# Power_v0.net
KiCad netlist of a schematic drawn in Altium Designer
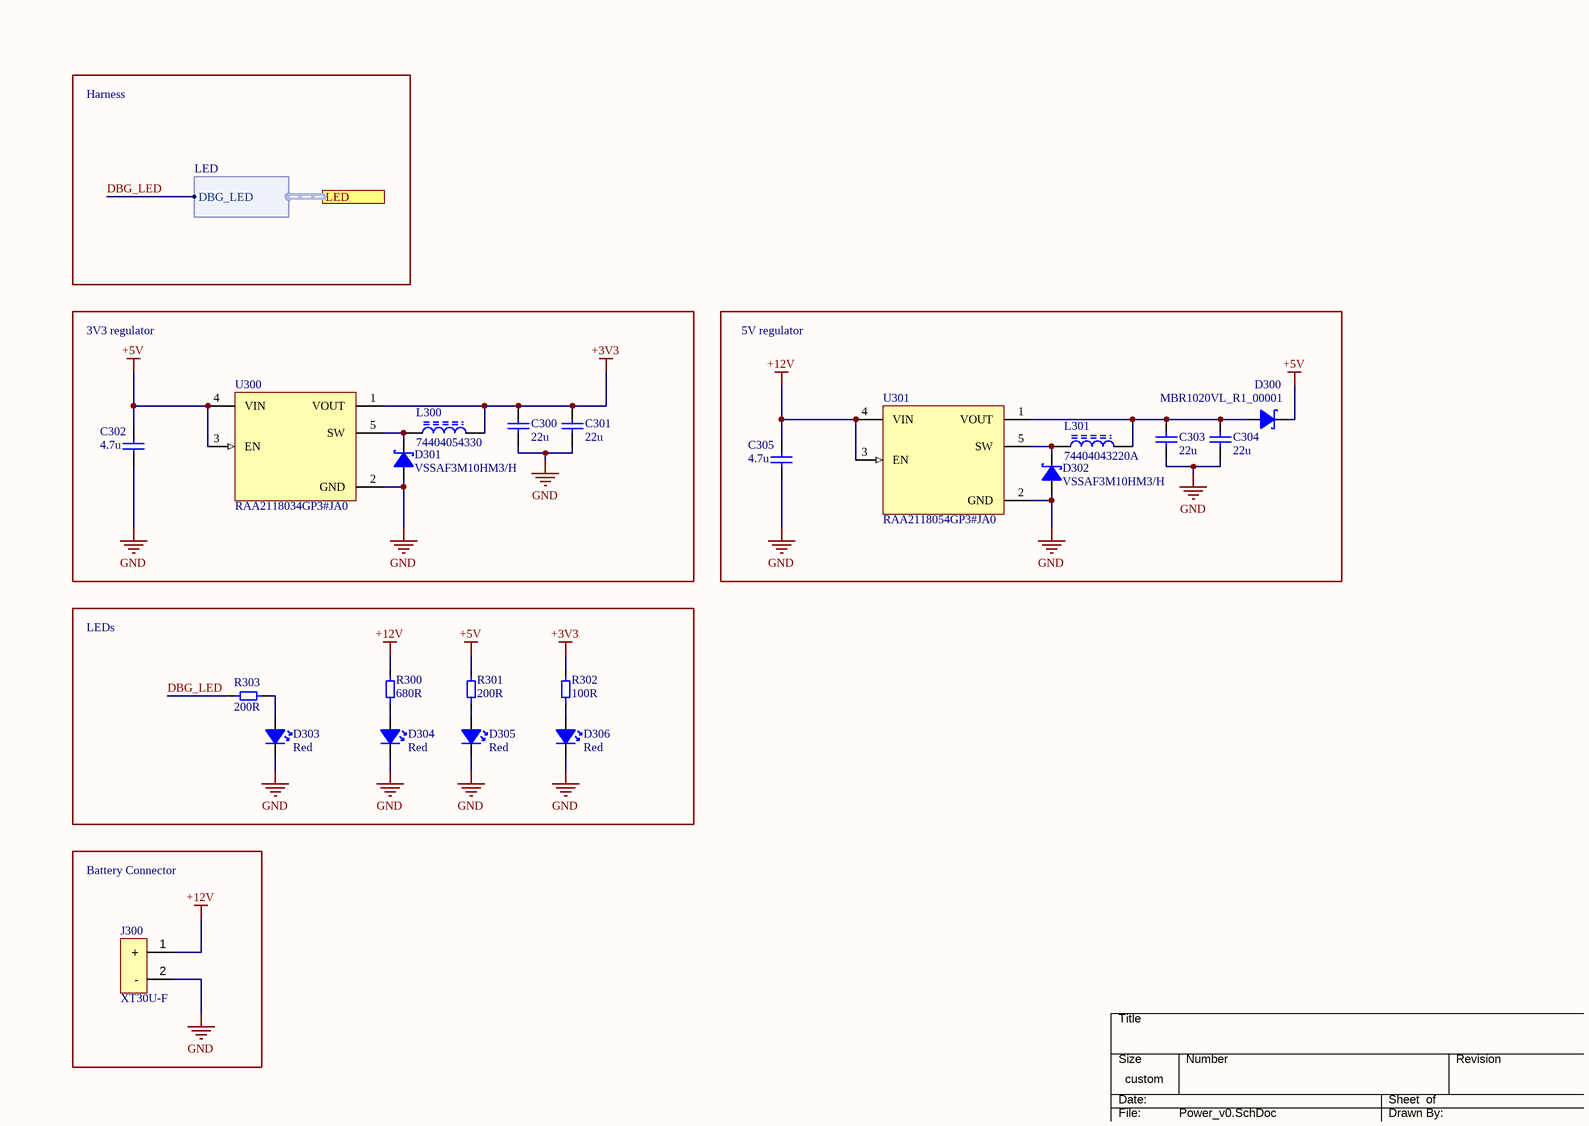
[diagram p0: Power_v0.SchDoc]

(export (version "E")
  (design (tool "Eeschema 10.0.6"))
  (components
    (comp (ref "C300")
      (value "22u")
      (footprint "MLCC_0603_M")
      (description "MLCC, 0603, 22u, 10%, 16V, X5R")
      (fields (field (name "TOLERANCE") "10%") (field (name "MANUFACTURER") "Any"))
      (libsource (lib "Krakul Vault") (part "CAPACITOR_NONPOL_IEC"))
    )
    (comp (ref "C301")
      (value "22u")
      (footprint "MLCC_0603_M")
      (description "MLCC, 0603, 22u, 10%, 16V, X5R")
      (fields (field (name "TOLERANCE") "10%") (field (name "MANUFACTURER") "Any"))
      (libsource (lib "Krakul Vault") (part "CAPACITOR_NONPOL_IEC"))
    )
    (comp (ref "C302")
      (value "4.7u")
      (footprint "MLCC_1206_M")
      (description "MLCC, 1206, 4.7u, 10%, 35V, X5R")
      (fields (field (name "VOLTAGE") "35V") (field (name "TOLERANCE") "10%"))
      (libsource (lib "Krakul Vault") (part "CAPACITOR_NONPOL_IEC"))
    )
    (comp (ref "C303")
      (value "22u")
      (footprint "MLCC_0603_M")
      (description "MLCC, 0603, 22u, 10%, 16V, X5R")
      (fields (field (name "TOLERANCE") "10%") (field (name "MANUFACTURER") "Any"))
      (libsource (lib "Krakul Vault") (part "CAPACITOR_NONPOL_IEC"))
    )
    (comp (ref "C304")
      (value "22u")
      (footprint "MLCC_0603_M")
      (description "MLCC, 0603, 22u, 10%, 16V, X5R")
      (fields (field (name "TOLERANCE") "10%") (field (name "MANUFACTURER") "Any"))
      (libsource (lib "Krakul Vault") (part "CAPACITOR_NONPOL_IEC"))
    )
    (comp (ref "C305")
      (value "4.7u")
      (footprint "MLCC_1206_M")
      (description "MLCC, 1206, 4.7u, 10%, 35V, X5R")
      (fields (field (name "VOLTAGE") "35V") (field (name "TOLERANCE") "10%"))
      (libsource (lib "Krakul Vault") (part "CAPACITOR_NONPOL_IEC"))
    )
    (comp (ref "D300")
      (value "MBR1020VL_R1_00001")
      (footprint "FP-MBR1020VL_R1_00001-MFG")
      (description "Rectifier Diode, Schottky, 1 Phase, 1 Element, 1A, 20V V(RRM), Silicon")
      (fields (field (name "MANUFACTURER") "Panjit"))
      (libsource (lib "Krakul Vault") (part "Schottky generic 2 pins"))
    )
    (comp (ref "D301")
      (value "VSSAF3M10HM3/H")
      (footprint "VSSAF3M10HM3_H-Footprint-1")
      (description "Rectifier Diode, Schottky, 1 Phase, 1 Element, 2.3A, 100V V(RRM), Silicon, DO-221AC")
      (libsource (lib "Krakul Vault") (part "Schottky generic 2 pins"))
    )
    (comp (ref "D302")
      (value "VSSAF3M10HM3/H")
      (footprint "VSSAF3M10HM3_H-Footprint-1")
      (description "Rectifier Diode, Schottky, 1 Phase, 1 Element, 2.3A, 100V V(RRM), Silicon, DO-221AC")
      (libsource (lib "Krakul Vault") (part "Schottky generic 2 pins"))
    )
    (comp (ref "D303")
      (value "Red")
      (footprint "0603 RED LED")
      (description "Generic red 0603 LED")
      (fields (field (name "PART NUMBER") "Any Red 0603 LED") (field (name "MANUFACTURER") "Any"))
      (libsource (lib "Krakul Vault") (part "LED generic"))
    )
    (comp (ref "D304")
      (value "Red")
      (footprint "0603 RED LED")
      (description "Generic red 0603 LED")
      (fields (field (name "PART NUMBER") "Any Red 0603 LED") (field (name "MANUFACTURER") "Any"))
      (libsource (lib "Krakul Vault") (part "LED generic"))
    )
    (comp (ref "D305")
      (value "Red")
      (footprint "0603 RED LED")
      (description "Generic red 0603 LED")
      (fields (field (name "PART NUMBER") "Any Red 0603 LED") (field (name "MANUFACTURER") "Any"))
      (libsource (lib "Krakul Vault") (part "LED generic"))
    )
    (comp (ref "D306")
      (value "Red")
      (footprint "0603 RED LED")
      (description "Generic red 0603 LED")
      (fields (field (name "PART NUMBER") "Any Red 0603 LED") (field (name "MANUFACTURER") "Any"))
      (libsource (lib "Krakul Vault") (part "LED generic"))
    )
    (comp (ref "J300")
      (value "XT30U-F")
      (footprint "XT30U-F")
      (description "Power Connector")
      (fields (field (name "MANUFACTURER") "AMASS"))
      (libsource (lib "Krakul Vault") (part "XT30U-F-Symbol-1"))
    )
    (comp (ref "L300")
      (value "74404054330")
      (footprint "WE-LQS_5040")
      (description "Inductor Power Semi-Shielded Wirewound 33uH 20% 100KHz 1.2A 0.188Ohm DCR 2020 Automotive T/R")
      (fields (field (name "MANUFACTURER") "Wurth Elektronik") (field (name "PART NUMBER") "74404043220A"))
      (libsource (lib "Krakul Vault") (part "INDUCTOR_SHIELDED"))
    )
    (comp (ref "L301")
      (value "74404043220A")
      (footprint "WE-LQS_4025")
      (description "General Purpose Inductor, 22uH, 20%, 1 Element, Nickel-zinc Ferrite-Core, SMD, 1616")
      (fields (field (name "MANUFACTURER") "Wurth Elektronik"))
      (libsource (lib "Krakul Vault") (part "INDUCTOR_SHIELDED"))
    )
    (comp (ref "R300")
      (value "680R")
      (footprint "Resistor_0603_M")
      (description "Resistor, 0603, 680R, 1%, 1/10W")
      (fields (field (name "POWER") "100mW") (field (name "TOLERANCE") "1%"))
      (libsource (lib "Krakul Vault") (part "RESISTOR_GENERIC_IEC"))
    )
    (comp (ref "R301")
      (value "200R")
      (footprint "Resistor_0603_M")
      (description "Resistor, 0603, 200R, 1%, 1/10W")
      (fields (field (name "TOLERANCE") "1%") (field (name "POWER") "100mW"))
      (libsource (lib "Krakul Vault") (part "RESISTOR_GENERIC_IEC"))
    )
    (comp (ref "R302")
      (value "100R")
      (footprint "Resistor_0603_M")
      (description "Resistor, 0603, 100R, ≤5%, ≥1/16W")
      (fields (field (name "MANUFACTURER") "Any"))
      (libsource (lib "Krakul Vault") (part "RESISTOR_GENERIC_IEC"))
    )
    (comp (ref "R303")
      (value "200R")
      (footprint "Resistor_0603_M")
      (description "Resistor, 0603, 200R, 1%, 1/10W")
      (fields (field (name "TOLERANCE") "1%") (field (name "POWER") "100mW"))
      (libsource (lib "Krakul Vault") (part "RESISTOR_GENERIC_IEC"))
    )
    (comp (ref "U300")
      (value "RAA2118034GP3#JA0")
      (footprint "P5_064B_MFG")
      (description "Switching Regulator, Current-mode, 0.3A, 170kHz Switching Freq-Max, PDSO5")
      (fields (field (name "MANUFACTURER") "Renesas / Intersil"))
      (libsource (lib "Krakul Vault") (part "RAA2118034GP3#JA0"))
    )
    (comp (ref "U301")
      (value "RAA2118054GP3#JA0")
      (footprint "P5_064B_MFG")
      (description "Switching Regulator, Current-mode, 0.3A, 230kHz Switching Freq-Max, PDSO5")
      (fields (field (name "MANUFACTURER") "Renesas / Intersil"))
      (libsource (lib "Krakul Vault") (part "04ef17e7ed04f306c00cc4b237f44d7"))
    )
  )
  (nets
    (net (code "2") (name "+3V3") (class "Default")
      (node (ref "C300") (pin "2") (pinfunction "2_2") (pintype "passive"))
      (node (ref "C301") (pin "2") (pinfunction "2_2") (pintype "passive"))
      (node (ref "L300") (pin "2") (pinfunction "2_2") (pintype "passive"))
      (node (ref "R302") (pin "2") (pinfunction "2_2") (pintype "passive"))
      (node (ref "U300") (pin "1") (pinfunction "VOUT_1") (pintype "power_in"))
    )
    (net (code "3") (name "+5V") (class "Default")
      (node (ref "C302") (pin "2") (pinfunction "2_2") (pintype "passive"))
      (node (ref "D300") (pin "1") (pinfunction "C_1") (pintype "passive"))
      (node (ref "R301") (pin "1") (pinfunction "1_1") (pintype "passive"))
      (node (ref "U300") (pin "3") (pinfunction "EN_3") (pintype "input"))
      (node (ref "U300") (pin "4") (pinfunction "VIN_4") (pintype "power_in"))
    )
    (net (code "4") (name "+12V") (class "Default")
      (node (ref "C305") (pin "2") (pinfunction "2_2") (pintype "passive"))
      (node (ref "J300") (pin "1") (pinfunction "+_1") (pintype "passive"))
      (node (ref "R300") (pin "2") (pinfunction "2_2") (pintype "passive"))
      (node (ref "U301") (pin "3") (pinfunction "EN_3") (pintype "input"))
      (node (ref "U301") (pin "4") (pinfunction "VIN_4") (pintype "power_in"))
    )
    (net (code "5") (name "/DBG_LED") (class "Default")
      (node (ref "R303") (pin "1") (pinfunction "1_1") (pintype "passive"))
    )
    (net (code "7") (name "GND") (class "Default")
      (node (ref "C300") (pin "1") (pinfunction "1_1") (pintype "passive"))
      (node (ref "C301") (pin "1") (pinfunction "1_1") (pintype "passive"))
      (node (ref "C302") (pin "1") (pinfunction "1_1") (pintype "passive"))
      (node (ref "C303") (pin "1") (pinfunction "1_1") (pintype "passive"))
      (node (ref "C304") (pin "1") (pinfunction "1_1") (pintype "passive"))
      (node (ref "C305") (pin "1") (pinfunction "1_1") (pintype "passive"))
      (node (ref "D301") (pin "2") (pinfunction "A_2") (pintype "passive"))
      (node (ref "D302") (pin "2") (pinfunction "A_2") (pintype "passive"))
      (node (ref "D303") (pin "1") (pinfunction "C_1") (pintype "passive"))
      (node (ref "D304") (pin "1") (pinfunction "C_1") (pintype "passive"))
      (node (ref "D305") (pin "1") (pinfunction "C_1") (pintype "passive"))
      (node (ref "D306") (pin "1") (pinfunction "C_1") (pintype "passive"))
      (node (ref "J300") (pin "2") (pinfunction "-_2") (pintype "passive"))
      (node (ref "U300") (pin "2") (pinfunction "GND_2") (pintype "power_in"))
      (node (ref "U301") (pin "2") (pinfunction "GND_2") (pintype "power_in"))
    )
    (net (code "8") (name "Net-(D300-A)") (class "Default")
      (node (ref "C303") (pin "2") (pinfunction "2_2") (pintype "passive"))
      (node (ref "C304") (pin "2") (pinfunction "2_2") (pintype "passive"))
      (node (ref "D300") (pin "2") (pinfunction "A_2") (pintype "passive"))
      (node (ref "L301") (pin "2") (pinfunction "2_2") (pintype "passive"))
      (node (ref "U301") (pin "1") (pinfunction "VOUT_1") (pintype "power_in"))
    )
    (net (code "9") (name "Net-(D301-C)") (class "Default")
      (node (ref "D301") (pin "1") (pinfunction "C_1") (pintype "passive"))
      (node (ref "L300") (pin "1") (pinfunction "1_1") (pintype "passive"))
      (node (ref "U300") (pin "5") (pinfunction "SW_5") (pintype "passive"))
    )
    (net (code "10") (name "Net-(D302-C)") (class "Default")
      (node (ref "D302") (pin "1") (pinfunction "C_1") (pintype "passive"))
      (node (ref "L301") (pin "1") (pinfunction "1_1") (pintype "passive"))
      (node (ref "U301") (pin "5") (pinfunction "SW_5") (pintype "passive"))
    )
    (net (code "11") (name "Net-(D303-A)") (class "Default")
      (node (ref "D303") (pin "2") (pinfunction "A_2") (pintype "passive"))
      (node (ref "R303") (pin "2") (pinfunction "2_2") (pintype "passive"))
    )
    (net (code "12") (name "Net-(D304-A)") (class "Default")
      (node (ref "D304") (pin "2") (pinfunction "A_2") (pintype "passive"))
      (node (ref "R300") (pin "1") (pinfunction "1_1") (pintype "passive"))
    )
    (net (code "13") (name "Net-(D305-A)") (class "Default")
      (node (ref "D305") (pin "2") (pinfunction "A_2") (pintype "passive"))
      (node (ref "R301") (pin "2") (pinfunction "2_2") (pintype "passive"))
    )
    (net (code "14") (name "Net-(D306-A)") (class "Default")
      (node (ref "D306") (pin "2") (pinfunction "A_2") (pintype "passive"))
      (node (ref "R302") (pin "1") (pinfunction "1_1") (pintype "passive"))
    )
  )
)
